# FPGAPower.net
KiCad netlist of a schematic drawn in Altium Designer
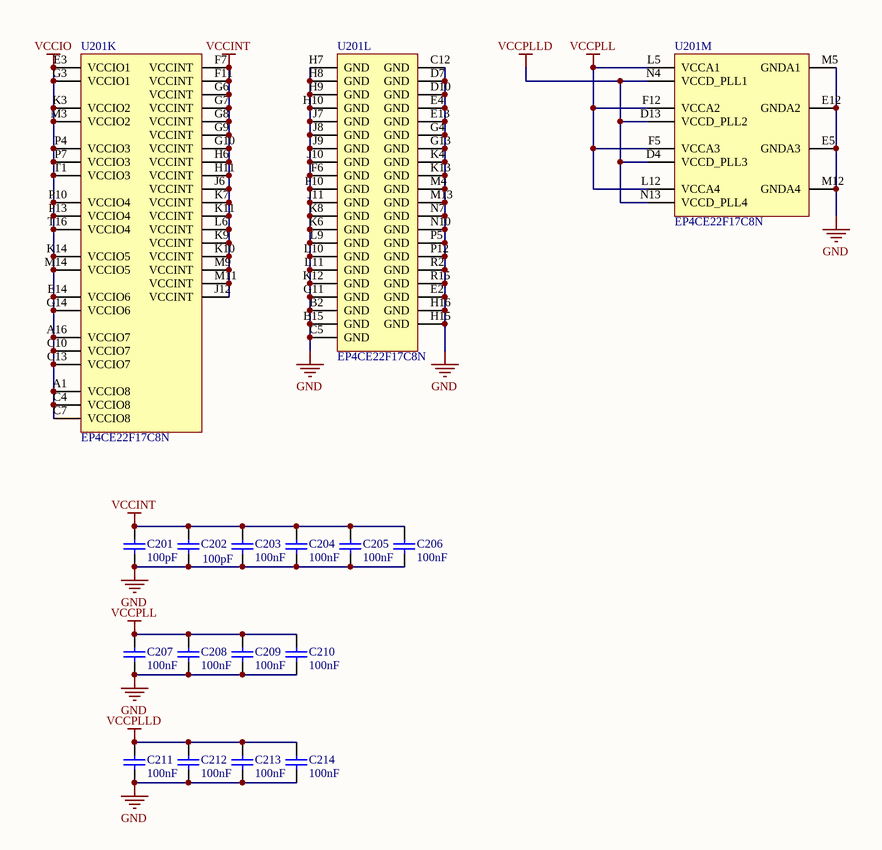
[diagram p0: FPGAPower.SchDoc]

(export (version "E")
  (design (tool "Eeschema 10.0.6"))
  (components
    (comp (ref "C201")
      (value "100pF")
      (footprint "0402C")
      (description "MLCC")
      (libsource (lib "Misc") (part "MLCC"))
    )
    (comp (ref "C202")
      (value "100pF")
      (footprint "0402C")
      (description "MLCC")
      (libsource (lib "Misc") (part "MLCC"))
    )
    (comp (ref "C203")
      (value "100nF")
      (footprint "0402C")
      (description "MLCC")
      (libsource (lib "Misc") (part "MLCC"))
    )
    (comp (ref "C204")
      (value "100nF")
      (footprint "0402C")
      (description "MLCC")
      (libsource (lib "Misc") (part "MLCC"))
    )
    (comp (ref "C205")
      (value "100nF")
      (footprint "0603C")
      (description "MLCC")
      (libsource (lib "Misc") (part "MLCC"))
    )
    (comp (ref "C206")
      (value "100nF")
      (footprint "0603C")
      (description "MLCC")
      (libsource (lib "Misc") (part "MLCC"))
    )
    (comp (ref "C207")
      (value "100nF")
      (footprint "0402C")
      (description "MLCC")
      (libsource (lib "Misc") (part "MLCC"))
    )
    (comp (ref "C208")
      (value "100nF")
      (footprint "0402C")
      (description "MLCC")
      (libsource (lib "Misc") (part "MLCC"))
    )
    (comp (ref "C209")
      (value "100nF")
      (footprint "0402C")
      (description "MLCC")
      (libsource (lib "Misc") (part "MLCC"))
    )
    (comp (ref "C210")
      (value "100nF")
      (footprint "0402C")
      (description "MLCC")
      (libsource (lib "Misc") (part "MLCC"))
    )
    (comp (ref "C211")
      (value "100nF")
      (footprint "0402C")
      (description "MLCC")
      (libsource (lib "Misc") (part "MLCC"))
    )
    (comp (ref "C212")
      (value "100nF")
      (footprint "0402C")
      (description "MLCC")
      (libsource (lib "Misc") (part "MLCC"))
    )
    (comp (ref "C213")
      (value "100nF")
      (footprint "0402C")
      (description "MLCC")
      (libsource (lib "Misc") (part "MLCC"))
    )
    (comp (ref "C214")
      (value "100nF")
      (footprint "0402C")
      (description "MLCC")
      (libsource (lib "Misc") (part "MLCC"))
    )
    (comp (ref "U201")
      (value "EP4CE22F17C8N")
      (footprint "FBGA256_A-155")
      (fields (field (name "MANUFACTURER") "Altera"))
      (libsource (lib "Altera Cyclone IV E") (part "EP4CE22F17C8N"))
    )
  )
  (nets
    (net (code "1") (name "GND") (class "Default")
      (node (ref "C201") (pin "1") (pinfunction "1_1") (pintype "passive"))
      (node (ref "C202") (pin "1") (pinfunction "1_1") (pintype "passive"))
      (node (ref "C203") (pin "1") (pinfunction "1_1") (pintype "passive"))
      (node (ref "C204") (pin "1") (pinfunction "1_1") (pintype "passive"))
      (node (ref "C205") (pin "1") (pinfunction "1_1") (pintype "passive"))
      (node (ref "C206") (pin "1") (pinfunction "1_1") (pintype "passive"))
      (node (ref "C207") (pin "1") (pinfunction "1_1") (pintype "passive"))
      (node (ref "C208") (pin "1") (pinfunction "1_1") (pintype "passive"))
      (node (ref "C209") (pin "1") (pinfunction "1_1") (pintype "passive"))
      (node (ref "C210") (pin "1") (pinfunction "1_1") (pintype "passive"))
      (node (ref "C211") (pin "1") (pinfunction "1_1") (pintype "passive"))
      (node (ref "C212") (pin "1") (pinfunction "1_1") (pintype "passive"))
      (node (ref "C213") (pin "1") (pinfunction "1_1") (pintype "passive"))
      (node (ref "C214") (pin "1") (pinfunction "1_1") (pintype "passive"))
      (node (ref "U201") (pin "B15") (pinfunction "GND_B15") (pintype "power_in"))
      (node (ref "U201") (pin "B2") (pinfunction "GND_B2") (pintype "power_in"))
      (node (ref "U201") (pin "C12") (pinfunction "GND_C12") (pintype "power_in"))
      (node (ref "U201") (pin "C5") (pinfunction "GND_C5") (pintype "power_in"))
      (node (ref "U201") (pin "D10") (pinfunction "GND_D10") (pintype "power_in"))
      (node (ref "U201") (pin "D7") (pinfunction "GND_D7") (pintype "power_in"))
      (node (ref "U201") (pin "E12") (pinfunction "GNDA2_E12") (pintype "power_in"))
      (node (ref "U201") (pin "E13") (pinfunction "GND_E13") (pintype "power_in"))
      (node (ref "U201") (pin "E2") (pinfunction "GND_E2") (pintype "power_in"))
      (node (ref "U201") (pin "E4") (pinfunction "GND_E4") (pintype "power_in"))
      (node (ref "U201") (pin "E5") (pinfunction "GNDA3_E5") (pintype "power_in"))
      (node (ref "U201") (pin "F10") (pinfunction "GND_F10") (pintype "power_in"))
      (node (ref "U201") (pin "F6") (pinfunction "GND_F6") (pintype "power_in"))
      (node (ref "U201") (pin "G11") (pinfunction "GND_G11") (pintype "power_in"))
      (node (ref "U201") (pin "G13") (pinfunction "GND_G13") (pintype "power_in"))
      (node (ref "U201") (pin "G4") (pinfunction "GND_G4") (pintype "power_in"))
      (node (ref "U201") (pin "H10") (pinfunction "GND_H10") (pintype "power_in"))
      (node (ref "U201") (pin "H15") (pinfunction "GND_H15") (pintype "power_in"))
      (node (ref "U201") (pin "H16") (pinfunction "GND_H16") (pintype "power_in"))
      (node (ref "U201") (pin "H7") (pinfunction "GND_H7") (pintype "power_in"))
      (node (ref "U201") (pin "H8") (pinfunction "GND_H8") (pintype "power_in"))
      (node (ref "U201") (pin "H9") (pinfunction "GND_H9") (pintype "power_in"))
      (node (ref "U201") (pin "J10") (pinfunction "GND_J10") (pintype "power_in"))
      (node (ref "U201") (pin "J11") (pinfunction "GND_J11") (pintype "power_in"))
      (node (ref "U201") (pin "J7") (pinfunction "GND_J7") (pintype "power_in"))
      (node (ref "U201") (pin "J8") (pinfunction "GND_J8") (pintype "power_in"))
      (node (ref "U201") (pin "J9") (pinfunction "GND_J9") (pintype "power_in"))
      (node (ref "U201") (pin "K12") (pinfunction "GND_K12") (pintype "power_in"))
      (node (ref "U201") (pin "K13") (pinfunction "GND_K13") (pintype "power_in"))
      (node (ref "U201") (pin "K4") (pinfunction "GND_K4") (pintype "power_in"))
      (node (ref "U201") (pin "K6") (pinfunction "GND_K6") (pintype "power_in"))
      (node (ref "U201") (pin "K8") (pinfunction "GND_K8") (pintype "power_in"))
      (node (ref "U201") (pin "L10") (pinfunction "GND_L10") (pintype "power_in"))
      (node (ref "U201") (pin "L11") (pinfunction "GND_L11") (pintype "power_in"))
      (node (ref "U201") (pin "L9") (pinfunction "GND_L9") (pintype "power_in"))
      (node (ref "U201") (pin "M12") (pinfunction "GNDA4_M12") (pintype "power_in"))
      (node (ref "U201") (pin "M13") (pinfunction "GND_M13") (pintype "power_in"))
      (node (ref "U201") (pin "M4") (pinfunction "GND_M4") (pintype "power_in"))
      (node (ref "U201") (pin "M5") (pinfunction "GNDA1_M5") (pintype "power_in"))
      (node (ref "U201") (pin "N10") (pinfunction "GND_N10") (pintype "power_in"))
      (node (ref "U201") (pin "N7") (pinfunction "GND_N7") (pintype "power_in"))
      (node (ref "U201") (pin "P12") (pinfunction "GND_P12") (pintype "power_in"))
      (node (ref "U201") (pin "P5") (pinfunction "GND_P5") (pintype "power_in"))
      (node (ref "U201") (pin "R15") (pinfunction "GND_R15") (pintype "power_in"))
      (node (ref "U201") (pin "R2") (pinfunction "GND_R2") (pintype "power_in"))
    )
    (net (code "2") (name "VCCINT") (class "Default")
      (node (ref "C201") (pin "2") (pinfunction "2_2") (pintype "passive"))
      (node (ref "C202") (pin "2") (pinfunction "2_2") (pintype "passive"))
      (node (ref "C203") (pin "2") (pinfunction "2_2") (pintype "passive"))
      (node (ref "C204") (pin "2") (pinfunction "2_2") (pintype "passive"))
      (node (ref "C205") (pin "2") (pinfunction "2_2") (pintype "passive"))
      (node (ref "C206") (pin "2") (pinfunction "2_2") (pintype "passive"))
      (node (ref "U201") (pin "F11") (pinfunction "VCCINT_F11") (pintype "power_in"))
      (node (ref "U201") (pin "F7") (pinfunction "VCCINT_F7") (pintype "power_in"))
      (node (ref "U201") (pin "G10") (pinfunction "VCCINT_G10") (pintype "power_in"))
      (node (ref "U201") (pin "G6") (pinfunction "VCCINT_G6") (pintype "power_in"))
      (node (ref "U201") (pin "G7") (pinfunction "VCCINT_G7") (pintype "power_in"))
      (node (ref "U201") (pin "G8") (pinfunction "VCCINT_G8") (pintype "power_in"))
      (node (ref "U201") (pin "G9") (pinfunction "VCCINT_G9") (pintype "power_in"))
      (node (ref "U201") (pin "H11") (pinfunction "VCCINT_H11") (pintype "power_in"))
      (node (ref "U201") (pin "H6") (pinfunction "VCCINT_H6") (pintype "power_in"))
      (node (ref "U201") (pin "J12") (pinfunction "VCCINT_J12") (pintype "power_in"))
      (node (ref "U201") (pin "J6") (pinfunction "VCCINT_J6") (pintype "power_in"))
      (node (ref "U201") (pin "K10") (pinfunction "VCCINT_K10") (pintype "power_in"))
      (node (ref "U201") (pin "K11") (pinfunction "VCCINT_K11") (pintype "power_in"))
      (node (ref "U201") (pin "K7") (pinfunction "VCCINT_K7") (pintype "power_in"))
      (node (ref "U201") (pin "K9") (pinfunction "VCCINT_K9") (pintype "power_in"))
      (node (ref "U201") (pin "L6") (pinfunction "VCCINT_L6") (pintype "power_in"))
      (node (ref "U201") (pin "M11") (pinfunction "VCCINT_M11") (pintype "power_in"))
      (node (ref "U201") (pin "M9") (pinfunction "VCCINT_M9") (pintype "power_in"))
    )
    (net (code "3") (name "VCCIO") (class "Default")
      (node (ref "U201") (pin "A1") (pinfunction "VCCIO8_A1") (pintype "power_in"))
      (node (ref "U201") (pin "A16") (pinfunction "VCCIO7_A16") (pintype "power_in"))
      (node (ref "U201") (pin "C10") (pinfunction "VCCIO7_C10") (pintype "power_in"))
      (node (ref "U201") (pin "C13") (pinfunction "VCCIO7_C13") (pintype "power_in"))
      (node (ref "U201") (pin "C4") (pinfunction "VCCIO8_C4") (pintype "power_in"))
      (node (ref "U201") (pin "C7") (pinfunction "VCCIO8_C7") (pintype "power_in"))
      (node (ref "U201") (pin "E14") (pinfunction "VCCIO6_E14") (pintype "power_in"))
      (node (ref "U201") (pin "E3") (pinfunction "VCCIO1_E3") (pintype "power_in"))
      (node (ref "U201") (pin "G14") (pinfunction "VCCIO6_G14") (pintype "power_in"))
      (node (ref "U201") (pin "G3") (pinfunction "VCCIO1_G3") (pintype "power_in"))
      (node (ref "U201") (pin "K14") (pinfunction "VCCIO5_K14") (pintype "power_in"))
      (node (ref "U201") (pin "K3") (pinfunction "VCCIO2_K3") (pintype "power_in"))
      (node (ref "U201") (pin "M14") (pinfunction "VCCIO5_M14") (pintype "power_in"))
      (node (ref "U201") (pin "M3") (pinfunction "VCCIO2_M3") (pintype "power_in"))
      (node (ref "U201") (pin "P10") (pinfunction "VCCIO4_P10") (pintype "power_in"))
      (node (ref "U201") (pin "P13") (pinfunction "VCCIO4_P13") (pintype "power_in"))
      (node (ref "U201") (pin "P4") (pinfunction "VCCIO3_P4") (pintype "power_in"))
      (node (ref "U201") (pin "P7") (pinfunction "VCCIO3_P7") (pintype "power_in"))
      (node (ref "U201") (pin "T1") (pinfunction "VCCIO3_T1") (pintype "power_in"))
      (node (ref "U201") (pin "T16") (pinfunction "VCCIO4_T16") (pintype "power_in"))
    )
    (net (code "4") (name "VCCPLL") (class "Default")
      (node (ref "C207") (pin "2") (pinfunction "2_2") (pintype "passive"))
      (node (ref "C208") (pin "2") (pinfunction "2_2") (pintype "passive"))
      (node (ref "C209") (pin "2") (pinfunction "2_2") (pintype "passive"))
      (node (ref "C210") (pin "2") (pinfunction "2_2") (pintype "passive"))
      (node (ref "U201") (pin "F12") (pinfunction "VCCA2_F12") (pintype "power_in"))
      (node (ref "U201") (pin "F5") (pinfunction "VCCA3_F5") (pintype "power_in"))
      (node (ref "U201") (pin "L12") (pinfunction "VCCA4_L12") (pintype "power_in"))
      (node (ref "U201") (pin "L5") (pinfunction "VCCA1_L5") (pintype "power_in"))
    )
    (net (code "5") (name "VCCPLLD") (class "Default")
      (node (ref "C211") (pin "2") (pinfunction "2_2") (pintype "passive"))
      (node (ref "C212") (pin "2") (pinfunction "2_2") (pintype "passive"))
      (node (ref "C213") (pin "2") (pinfunction "2_2") (pintype "passive"))
      (node (ref "C214") (pin "2") (pinfunction "2_2") (pintype "passive"))
      (node (ref "U201") (pin "D13") (pinfunction "VCCD_PLL2_D13") (pintype "power_in"))
      (node (ref "U201") (pin "D4") (pinfunction "VCCD_PLL3_D4") (pintype "power_in"))
      (node (ref "U201") (pin "N13") (pinfunction "VCCD_PLL4_N13") (pintype "power_in"))
      (node (ref "U201") (pin "N4") (pinfunction "VCCD_PLL1_N4") (pintype "power_in"))
    )
  )
)
